# SiC780.net
KiCad netlist of a schematic drawn in Altium Designer
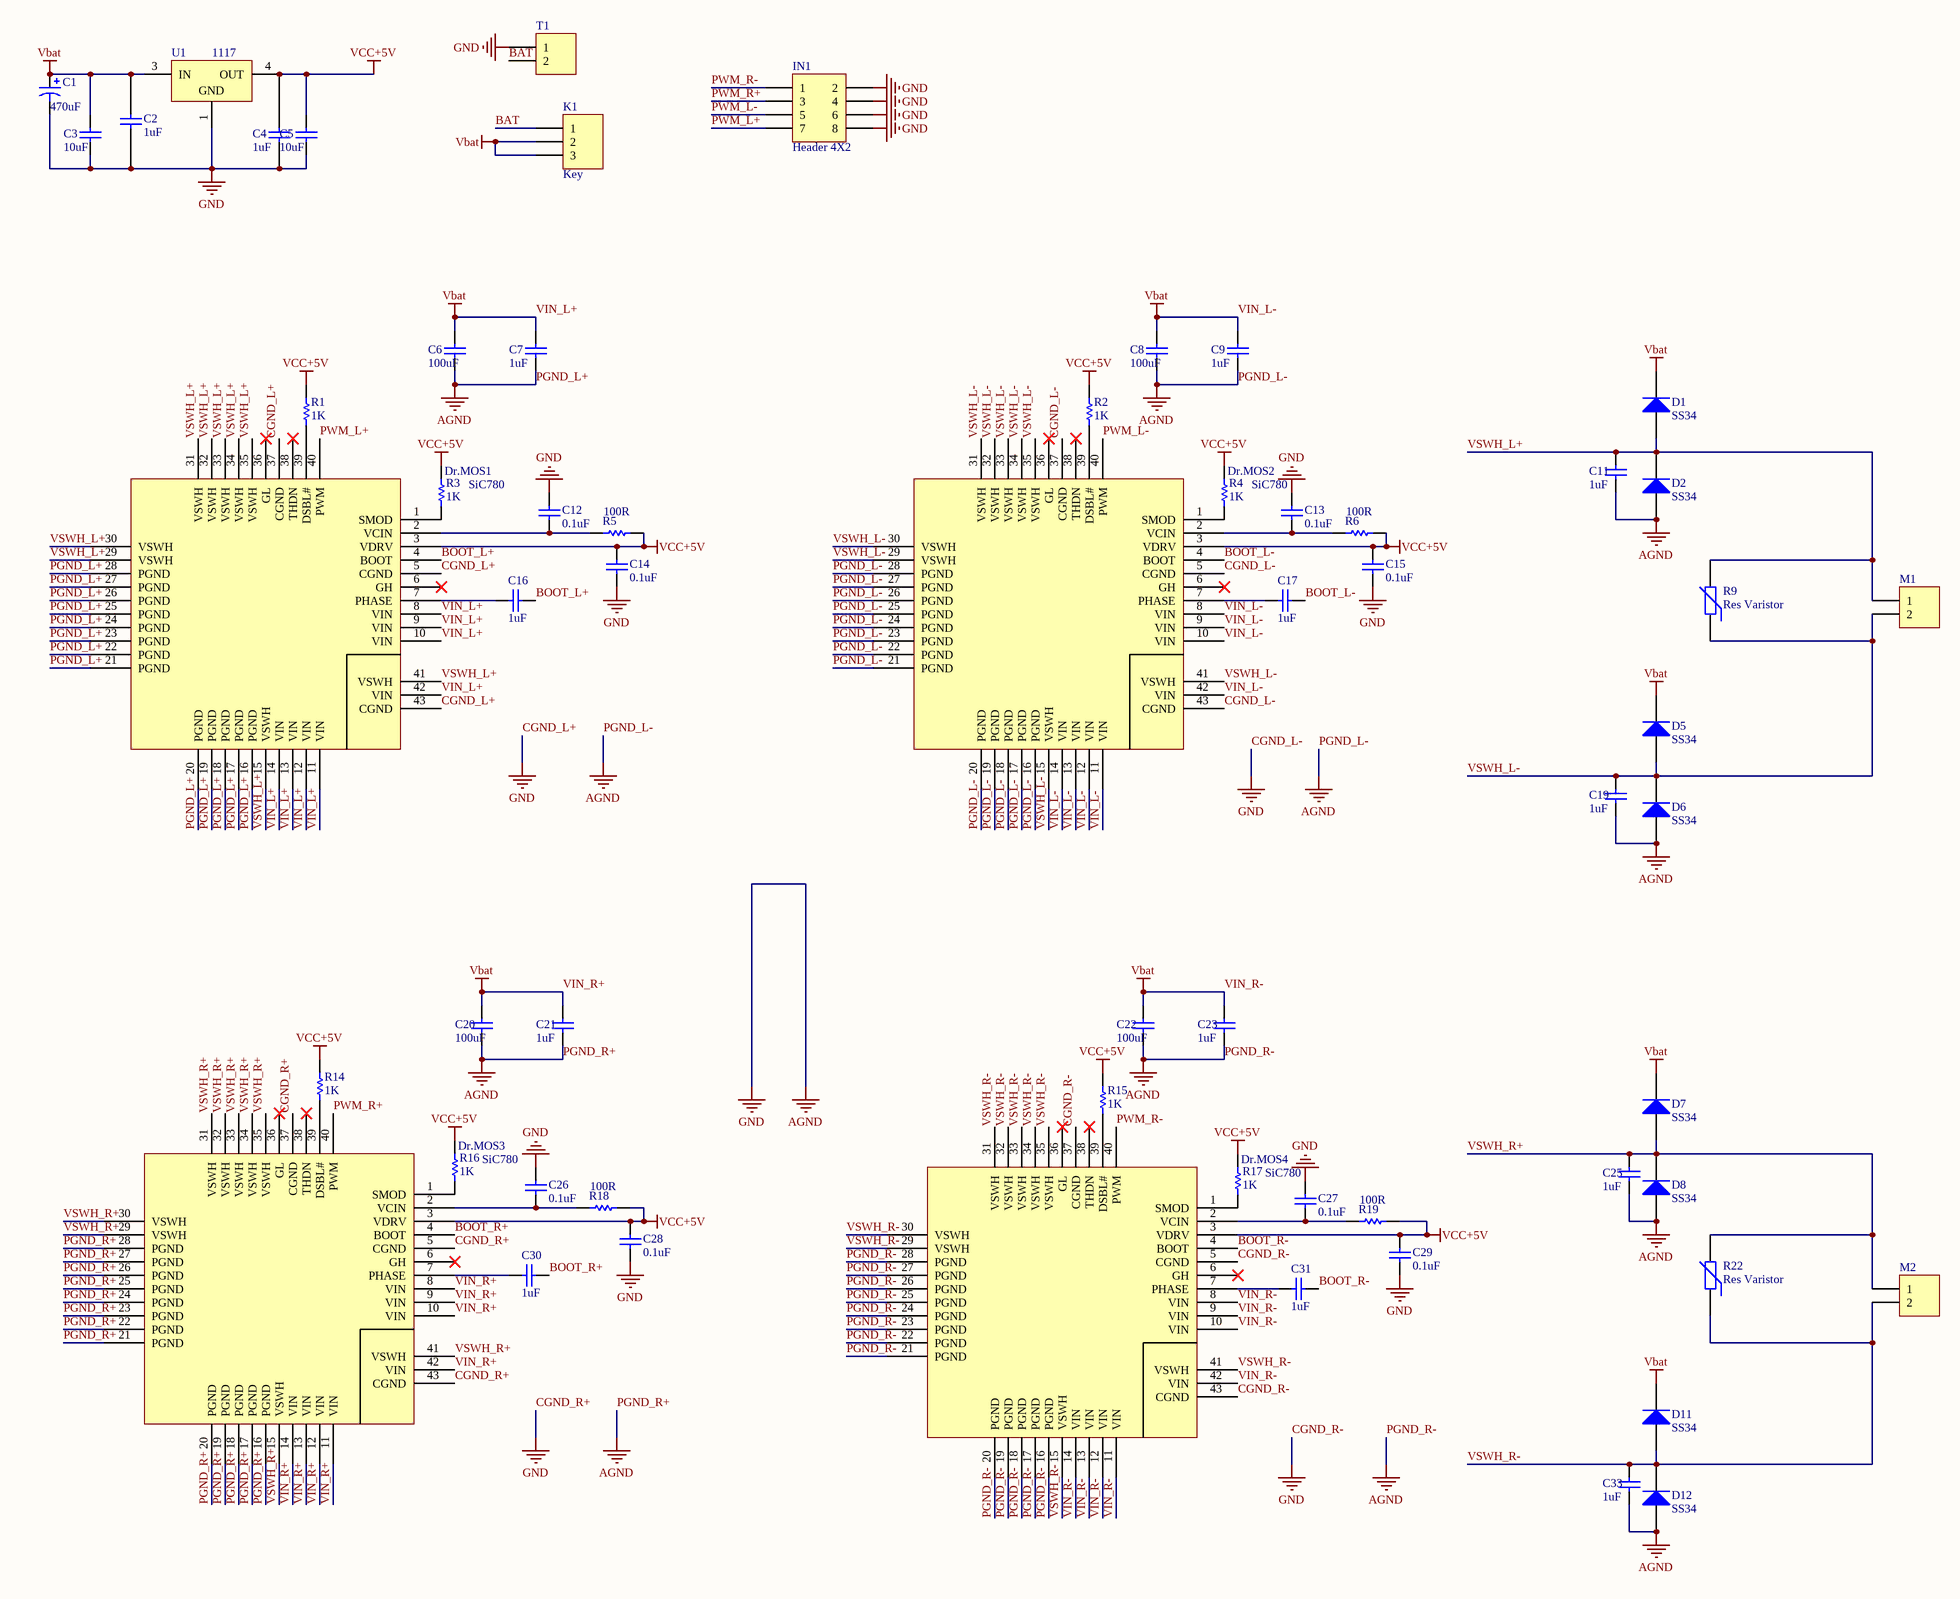
[diagram p0: SiC780驱动.SchDoc]

(export (version "E")
  (design (tool "Eeschema 10.0.6"))
  (components
    (comp (ref "C1")
      (value "470uF")
      (footprint "CAP")
      (description "Polarized Capacitor (Surface Mount)")
      (fields (field (name "Comment") "470uf") (field (name "PUBLISHER") "Altium Limited"))
      (libsource (lib "Miscellaneous Devices") (part "Cap Pol3"))
    )
    (comp (ref "C2")
      (value "1uF")
      (footprint "0603_C")
      (description "Capacitor")
      (fields (field (name "PUBLISHER") "Altium Limited"))
      (libsource (lib "Miscellaneous Devices") (part "Cap"))
    )
    (comp (ref "C3")
      (value "10uF")
      (footprint "1206_C")
      (description "Capacitor")
      (fields (field (name "PUBLISHER") "Altium Limited"))
      (libsource (lib "Miscellaneous Devices") (part "Cap"))
    )
    (comp (ref "C4")
      (value "1uF")
      (footprint "0603_C")
      (description "Capacitor")
      (fields (field (name "PUBLISHER") "Altium Limited"))
      (libsource (lib "Miscellaneous Devices") (part "Cap"))
    )
    (comp (ref "C5")
      (value "10uF")
      (footprint "1206_C")
      (description "Capacitor")
      (fields (field (name "PUBLISHER") "Altium Limited"))
      (libsource (lib "Miscellaneous Devices") (part "Cap"))
    )
    (comp (ref "C6")
      (value "100uF")
      (footprint "1206_C")
      (description "Capacitor")
      (fields (field (name "PUBLISHER") "Altium Limited"))
      (libsource (lib "Miscellaneous Devices") (part "Cap"))
    )
    (comp (ref "C7")
      (value "1uF")
      (footprint "0603_C")
      (description "Capacitor")
      (fields (field (name "PUBLISHER") "Altium Limited"))
      (libsource (lib "Miscellaneous Devices") (part "Cap"))
    )
    (comp (ref "C8")
      (value "100uF")
      (footprint "1206_C")
      (description "Capacitor")
      (fields (field (name "PUBLISHER") "Altium Limited"))
      (libsource (lib "Miscellaneous Devices") (part "Cap"))
    )
    (comp (ref "C9")
      (value "1uF")
      (footprint "0603_C")
      (description "Capacitor")
      (fields (field (name "PUBLISHER") "Altium Limited"))
      (libsource (lib "Miscellaneous Devices") (part "Cap"))
    )
    (comp (ref "C11")
      (value "1uF")
      (footprint "0603_C")
      (description "Capacitor")
      (fields (field (name "PUBLISHER") "Altium Limited"))
      (libsource (lib "Miscellaneous Devices") (part "Cap"))
    )
    (comp (ref "C12")
      (value "0.1uF")
      (footprint "0603_C")
      (description "Capacitor")
      (fields (field (name "PUBLISHER") "Altium Limited"))
      (libsource (lib "Miscellaneous Devices") (part "Cap"))
    )
    (comp (ref "C13")
      (value "0.1uF")
      (footprint "0603_C")
      (description "Capacitor")
      (fields (field (name "PUBLISHER") "Altium Limited"))
      (libsource (lib "Miscellaneous Devices") (part "Cap"))
    )
    (comp (ref "C14")
      (value "0.1uF")
      (footprint "0603_C")
      (description "Capacitor")
      (fields (field (name "PUBLISHER") "Altium Limited"))
      (libsource (lib "Miscellaneous Devices") (part "Cap"))
    )
    (comp (ref "C15")
      (value "0.1uF")
      (footprint "0603_C")
      (description "Capacitor")
      (fields (field (name "PUBLISHER") "Altium Limited"))
      (libsource (lib "Miscellaneous Devices") (part "Cap"))
    )
    (comp (ref "C16")
      (value "1uF")
      (footprint "0603_C")
      (description "Capacitor")
      (fields (field (name "Comment") "0.1uF") (field (name "PUBLISHER") "Altium Limited"))
      (libsource (lib "Miscellaneous Devices") (part "Cap"))
    )
    (comp (ref "C17")
      (value "1uF")
      (footprint "0603_C")
      (description "Capacitor")
      (fields (field (name "Comment") "0.1uF") (field (name "PUBLISHER") "Altium Limited"))
      (libsource (lib "Miscellaneous Devices") (part "Cap"))
    )
    (comp (ref "C19")
      (value "1uF")
      (footprint "0603_C")
      (description "Capacitor")
      (fields (field (name "PUBLISHER") "Altium Limited"))
      (libsource (lib "Miscellaneous Devices") (part "Cap"))
    )
    (comp (ref "C20")
      (value "100uF")
      (footprint "1206_C")
      (description "Capacitor")
      (fields (field (name "PUBLISHER") "Altium Limited"))
      (libsource (lib "Miscellaneous Devices") (part "Cap"))
    )
    (comp (ref "C21")
      (value "1uF")
      (footprint "0603_C")
      (description "Capacitor")
      (fields (field (name "PUBLISHER") "Altium Limited"))
      (libsource (lib "Miscellaneous Devices") (part "Cap"))
    )
    (comp (ref "C22")
      (value "100uF")
      (footprint "1206_C")
      (description "Capacitor")
      (fields (field (name "PUBLISHER") "Altium Limited"))
      (libsource (lib "Miscellaneous Devices") (part "Cap"))
    )
    (comp (ref "C23")
      (value "1uF")
      (footprint "0603_C")
      (description "Capacitor")
      (fields (field (name "PUBLISHER") "Altium Limited"))
      (libsource (lib "Miscellaneous Devices") (part "Cap"))
    )
    (comp (ref "C25")
      (value "1uF")
      (footprint "0603_C")
      (description "Capacitor")
      (fields (field (name "PUBLISHER") "Altium Limited"))
      (libsource (lib "Miscellaneous Devices") (part "Cap"))
    )
    (comp (ref "C26")
      (value "0.1uF")
      (footprint "0603_C")
      (description "Capacitor")
      (fields (field (name "PUBLISHER") "Altium Limited"))
      (libsource (lib "Miscellaneous Devices") (part "Cap"))
    )
    (comp (ref "C27")
      (value "0.1uF")
      (footprint "0603_C")
      (description "Capacitor")
      (fields (field (name "PUBLISHER") "Altium Limited"))
      (libsource (lib "Miscellaneous Devices") (part "Cap"))
    )
    (comp (ref "C28")
      (value "0.1uF")
      (footprint "0603_C")
      (description "Capacitor")
      (fields (field (name "PUBLISHER") "Altium Limited"))
      (libsource (lib "Miscellaneous Devices") (part "Cap"))
    )
    (comp (ref "C29")
      (value "0.1uF")
      (footprint "0603_C")
      (description "Capacitor")
      (fields (field (name "PUBLISHER") "Altium Limited"))
      (libsource (lib "Miscellaneous Devices") (part "Cap"))
    )
    (comp (ref "C30")
      (value "1uF")
      (footprint "0603_C")
      (description "Capacitor")
      (fields (field (name "Comment") "0.1uF") (field (name "PUBLISHER") "Altium Limited"))
      (libsource (lib "Miscellaneous Devices") (part "Cap"))
    )
    (comp (ref "C31")
      (value "1uF")
      (footprint "0603_C")
      (description "Capacitor")
      (fields (field (name "Comment") "0.1uF") (field (name "PUBLISHER") "Altium Limited"))
      (libsource (lib "Miscellaneous Devices") (part "Cap"))
    )
    (comp (ref "C33")
      (value "1uF")
      (footprint "0603_C")
      (description "Capacitor")
      (fields (field (name "PUBLISHER") "Altium Limited"))
      (libsource (lib "Miscellaneous Devices") (part "Cap"))
    )
    (comp (ref "D1")
      (value "SS34")
      (footprint "Diode-1N5189  5*1.5mm")
      (libsource (lib "12届光电双电机MOS驱动") (part "Diode"))
    )
    (comp (ref "D2")
      (value "SS34")
      (footprint "Diode-1N5189  5*1.5mm")
      (libsource (lib "12届光电双电机MOS驱动") (part "Diode"))
    )
    (comp (ref "D5")
      (value "SS34")
      (footprint "Diode-1N5189  5*1.5mm")
      (libsource (lib "12届光电双电机MOS驱动") (part "Diode"))
    )
    (comp (ref "D6")
      (value "SS34")
      (footprint "Diode-1N5189  5*1.5mm")
      (libsource (lib "12届光电双电机MOS驱动") (part "Diode"))
    )
    (comp (ref "D7")
      (value "SS34")
      (footprint "Diode-1N5189  5*1.5mm")
      (libsource (lib "12届光电双电机MOS驱动") (part "Diode"))
    )
    (comp (ref "D8")
      (value "SS34")
      (footprint "Diode-1N5189  5*1.5mm")
      (libsource (lib "12届光电双电机MOS驱动") (part "Diode"))
    )
    (comp (ref "D11")
      (value "SS34")
      (footprint "Diode-1N5189  5*1.5mm")
      (libsource (lib "12届光电双电机MOS驱动") (part "Diode"))
    )
    (comp (ref "D12")
      (value "SS34")
      (footprint "Diode-1N5189  5*1.5mm")
      (libsource (lib "12届光电双电机MOS驱动") (part "Diode"))
    )
    (comp (ref "Dr.MOS1")
      (value "SiC780")
      (footprint "SiC780_new")
      (libsource (lib "SiC780") (part "SiC780"))
    )
    (comp (ref "Dr.MOS2")
      (value "SiC780")
      (footprint "SiC780_new")
      (libsource (lib "SiC780") (part "SiC780"))
    )
    (comp (ref "Dr.MOS3")
      (value "SiC780")
      (footprint "SiC780_new")
      (libsource (lib "SiC780") (part "SiC780"))
    )
    (comp (ref "Dr.MOS4")
      (value "SiC780")
      (footprint "SiC780_new")
      (libsource (lib "SiC780") (part "SiC780"))
    )
    (comp (ref "IN1")
      (value "Header 4X2")
      (footprint "HDR2X4_3D")
      (description "Header, 4-Pin, Dual row")
      (fields (field (name "PUBLISHER") "Altium Limited"))
      (libsource (lib "Miscellaneous Connectors") (part "Header 4X2"))
    )
    (comp (ref "K1")
      (value "Key")
      (footprint "SW-M")
      (description "Header, 3-Pin")
      (fields (field (name "PUBLISHER") "Altium Limited"))
      (libsource (lib "Miscellaneous Connectors") (part "Header 3"))
    )
    (comp (ref "M1")
      (value "~")
      (footprint "KF301-2P")
      (description "Header, 2-Pin")
      (fields (field (name "PUBLISHER") "Altium Limited"))
      (libsource (lib "Miscellaneous Connectors") (part "Header 2"))
    )
    (comp (ref "M2")
      (value "~")
      (footprint "KF301-2P")
      (description "Header, 2-Pin")
      (fields (field (name "PUBLISHER") "Altium Limited"))
      (libsource (lib "Miscellaneous Connectors") (part "Header 2"))
    )
    (comp (ref "R1")
      (value "1K")
      (footprint "R0603")
      (description "Resistor")
      (fields (field (name "PUBLISHER") "Altium Limited"))
      (libsource (lib "Miscellaneous Devices") (part "Res1"))
    )
    (comp (ref "R2")
      (value "1K")
      (footprint "R0603")
      (description "Resistor")
      (fields (field (name "PUBLISHER") "Altium Limited"))
      (libsource (lib "Miscellaneous Devices") (part "Res1"))
    )
    (comp (ref "R3")
      (value "1K")
      (footprint "R0603")
      (description "Resistor")
      (fields (field (name "PUBLISHER") "Altium Limited"))
      (libsource (lib "Miscellaneous Devices") (part "Res1"))
    )
    (comp (ref "R4")
      (value "1K")
      (footprint "R0603")
      (description "Resistor")
      (fields (field (name "PUBLISHER") "Altium Limited"))
      (libsource (lib "Miscellaneous Devices") (part "Res1"))
    )
    (comp (ref "R5")
      (value "100R")
      (footprint "R0603")
      (description "Resistor")
      (fields (field (name "PUBLISHER") "Altium Limited"))
      (libsource (lib "Miscellaneous Devices") (part "Res1"))
    )
    (comp (ref "R6")
      (value "100R")
      (footprint "R0603")
      (description "Resistor")
      (fields (field (name "PUBLISHER") "Altium Limited"))
      (libsource (lib "Miscellaneous Devices") (part "Res1"))
    )
    (comp (ref "R9")
      (value "Res Varistor")
      (footprint "6-0805_N")
      (description "Varistor (Voltage-Sensitive Resistor)")
      (fields (field (name "PUBLISHER") "Altium Limited"))
      (libsource (lib "Miscellaneous Devices") (part "Res Varistor"))
    )
    (comp (ref "R14")
      (value "1K")
      (footprint "R0603")
      (description "Resistor")
      (fields (field (name "PUBLISHER") "Altium Limited"))
      (libsource (lib "Miscellaneous Devices") (part "Res1"))
    )
    (comp (ref "R15")
      (value "1K")
      (footprint "R0603")
      (description "Resistor")
      (fields (field (name "PUBLISHER") "Altium Limited"))
      (libsource (lib "Miscellaneous Devices") (part "Res1"))
    )
    (comp (ref "R16")
      (value "1K")
      (footprint "R0603")
      (description "Resistor")
      (fields (field (name "PUBLISHER") "Altium Limited"))
      (libsource (lib "Miscellaneous Devices") (part "Res1"))
    )
    (comp (ref "R17")
      (value "1K")
      (footprint "R0603")
      (description "Resistor")
      (fields (field (name "PUBLISHER") "Altium Limited"))
      (libsource (lib "Miscellaneous Devices") (part "Res1"))
    )
    (comp (ref "R18")
      (value "100R")
      (footprint "R0603")
      (description "Resistor")
      (fields (field (name "PUBLISHER") "Altium Limited"))
      (libsource (lib "Miscellaneous Devices") (part "Res1"))
    )
    (comp (ref "R19")
      (value "100R")
      (footprint "R0603")
      (description "Resistor")
      (fields (field (name "PUBLISHER") "Altium Limited"))
      (libsource (lib "Miscellaneous Devices") (part "Res1"))
    )
    (comp (ref "R22")
      (value "Res Varistor")
      (footprint "6-0805_N")
      (description "Varistor (Voltage-Sensitive Resistor)")
      (fields (field (name "PUBLISHER") "Altium Limited"))
      (libsource (lib "Miscellaneous Devices") (part "Res Varistor"))
    )
    (comp (ref "T1")
      (value "~")
      (footprint "KF301-2P")
      (description "Header, 2-Pin")
      (fields (field (name "PUBLISHER") "Altium Limited"))
      (libsource (lib "Miscellaneous Connectors") (part "Header 2"))
    )
    (comp (ref "U1")
      (value "1117")
      (footprint "SOT223_N")
      (description "800mA Low-Dropout Linear Regulator")
      (fields
        (field (name "PARTNUMBER") "LM1117DT-3.3")
        (field (name "MANUFACTURER") "National Semiconductor")
        (field (name "PUBLISHER") "Altium Limited")
      )
      (libsource (lib "NSC LDO") (part "LM1117DT-3.3"))
    )
  )
  (nets
    (net (code "1") (name "/BAT") (class "Default")
      (node (ref "K1") (pin "1") (pinfunction "1_1") (pintype "passive"))
      (node (ref "T1") (pin "2") (pinfunction "2_2") (pintype "passive"))
    )
    (net (code "2") (name "/BOOT_L+") (class "Default")
      (node (ref "C16") (pin "2") (pinfunction "2_2") (pintype "passive"))
      (node (ref "Dr.MOS1") (pin "4") (pinfunction "BOOT_4") (pintype "passive"))
    )
    (net (code "3") (name "/BOOT_L-") (class "Default")
      (node (ref "C17") (pin "2") (pinfunction "2_2") (pintype "passive"))
      (node (ref "Dr.MOS2") (pin "4") (pinfunction "BOOT_4") (pintype "passive"))
    )
    (net (code "4") (name "/BOOT_R+") (class "Default")
      (node (ref "C30") (pin "2") (pinfunction "2_2") (pintype "passive"))
      (node (ref "Dr.MOS3") (pin "4") (pinfunction "BOOT_4") (pintype "passive"))
    )
    (net (code "5") (name "/BOOT_R-") (class "Default")
      (node (ref "C31") (pin "2") (pinfunction "2_2") (pintype "passive"))
      (node (ref "Dr.MOS4") (pin "4") (pinfunction "BOOT_4") (pintype "passive"))
    )
    (net (code "6") (name "/PWM_L+") (class "Default")
      (node (ref "Dr.MOS1") (pin "40") (pinfunction "PWM_40") (pintype "passive"))
      (node (ref "IN1") (pin "7") (pinfunction "7_7") (pintype "passive"))
    )
    (net (code "7") (name "/PWM_L-") (class "Default")
      (node (ref "Dr.MOS2") (pin "40") (pinfunction "PWM_40") (pintype "passive"))
      (node (ref "IN1") (pin "5") (pinfunction "5_5") (pintype "passive"))
    )
    (net (code "8") (name "/PWM_R+") (class "Default")
      (node (ref "Dr.MOS3") (pin "40") (pinfunction "PWM_40") (pintype "passive"))
      (node (ref "IN1") (pin "3") (pinfunction "3_3") (pintype "passive"))
    )
    (net (code "9") (name "/PWM_R-") (class "Default")
      (node (ref "Dr.MOS4") (pin "40") (pinfunction "PWM_40") (pintype "passive"))
      (node (ref "IN1") (pin "1") (pinfunction "1_1") (pintype "passive"))
    )
    (net (code "10") (name "/VSWH_L+") (class "Default")
      (node (ref "C11") (pin "1") (pinfunction "1_1") (pintype "passive"))
      (node (ref "D1") (pin "1") (pinfunction "A_1") (pintype "passive"))
      (node (ref "D2") (pin "2") (pinfunction "K_2") (pintype "passive"))
      (node (ref "Dr.MOS1") (pin "15") (pinfunction "VSWH_15") (pintype "passive"))
      (node (ref "Dr.MOS1") (pin "29") (pinfunction "VSWH_29") (pintype "passive"))
      (node (ref "Dr.MOS1") (pin "30") (pinfunction "VSWH_30") (pintype "passive"))
      (node (ref "Dr.MOS1") (pin "31") (pinfunction "VSWH_31") (pintype "passive"))
      (node (ref "Dr.MOS1") (pin "32") (pinfunction "VSWH_32") (pintype "passive"))
      (node (ref "Dr.MOS1") (pin "33") (pinfunction "VSWH_33") (pintype "passive"))
      (node (ref "Dr.MOS1") (pin "34") (pinfunction "VSWH_34") (pintype "passive"))
      (node (ref "Dr.MOS1") (pin "35") (pinfunction "VSWH_35") (pintype "passive"))
      (node (ref "Dr.MOS1") (pin "41") (pinfunction "VSWH_41") (pintype "passive"))
      (node (ref "M1") (pin "1") (pinfunction "1_1") (pintype "passive"))
      (node (ref "R9") (pin "2") (pinfunction "2_2") (pintype "passive"))
    )
    (net (code "11") (name "/VSWH_L-") (class "Default")
      (node (ref "C19") (pin "1") (pinfunction "1_1") (pintype "passive"))
      (node (ref "D5") (pin "1") (pinfunction "A_1") (pintype "passive"))
      (node (ref "D6") (pin "2") (pinfunction "K_2") (pintype "passive"))
      (node (ref "Dr.MOS2") (pin "15") (pinfunction "VSWH_15") (pintype "passive"))
      (node (ref "Dr.MOS2") (pin "29") (pinfunction "VSWH_29") (pintype "passive"))
      (node (ref "Dr.MOS2") (pin "30") (pinfunction "VSWH_30") (pintype "passive"))
      (node (ref "Dr.MOS2") (pin "31") (pinfunction "VSWH_31") (pintype "passive"))
      (node (ref "Dr.MOS2") (pin "32") (pinfunction "VSWH_32") (pintype "passive"))
      (node (ref "Dr.MOS2") (pin "33") (pinfunction "VSWH_33") (pintype "passive"))
      (node (ref "Dr.MOS2") (pin "34") (pinfunction "VSWH_34") (pintype "passive"))
      (node (ref "Dr.MOS2") (pin "35") (pinfunction "VSWH_35") (pintype "passive"))
      (node (ref "Dr.MOS2") (pin "41") (pinfunction "VSWH_41") (pintype "passive"))
      (node (ref "M1") (pin "2") (pinfunction "2_2") (pintype "passive"))
      (node (ref "R9") (pin "1") (pinfunction "1_1") (pintype "passive"))
    )
    (net (code "12") (name "/VSWH_R+") (class "Default")
      (node (ref "C25") (pin "1") (pinfunction "1_1") (pintype "passive"))
      (node (ref "D7") (pin "1") (pinfunction "A_1") (pintype "passive"))
      (node (ref "D8") (pin "2") (pinfunction "K_2") (pintype "passive"))
      (node (ref "Dr.MOS3") (pin "15") (pinfunction "VSWH_15") (pintype "passive"))
      (node (ref "Dr.MOS3") (pin "29") (pinfunction "VSWH_29") (pintype "passive"))
      (node (ref "Dr.MOS3") (pin "30") (pinfunction "VSWH_30") (pintype "passive"))
      (node (ref "Dr.MOS3") (pin "31") (pinfunction "VSWH_31") (pintype "passive"))
      (node (ref "Dr.MOS3") (pin "32") (pinfunction "VSWH_32") (pintype "passive"))
      (node (ref "Dr.MOS3") (pin "33") (pinfunction "VSWH_33") (pintype "passive"))
      (node (ref "Dr.MOS3") (pin "34") (pinfunction "VSWH_34") (pintype "passive"))
      (node (ref "Dr.MOS3") (pin "35") (pinfunction "VSWH_35") (pintype "passive"))
      (node (ref "Dr.MOS3") (pin "41") (pinfunction "VSWH_41") (pintype "passive"))
      (node (ref "M2") (pin "1") (pinfunction "1_1") (pintype "passive"))
      (node (ref "R22") (pin "2") (pinfunction "2_2") (pintype "passive"))
    )
    (net (code "13") (name "/VSWH_R-") (class "Default")
      (node (ref "C33") (pin "1") (pinfunction "1_1") (pintype "passive"))
      (node (ref "D11") (pin "1") (pinfunction "A_1") (pintype "passive"))
      (node (ref "D12") (pin "2") (pinfunction "K_2") (pintype "passive"))
      (node (ref "Dr.MOS4") (pin "15") (pinfunction "VSWH_15") (pintype "passive"))
      (node (ref "Dr.MOS4") (pin "29") (pinfunction "VSWH_29") (pintype "passive"))
      (node (ref "Dr.MOS4") (pin "30") (pinfunction "VSWH_30") (pintype "passive"))
      (node (ref "Dr.MOS4") (pin "31") (pinfunction "VSWH_31") (pintype "passive"))
      (node (ref "Dr.MOS4") (pin "32") (pinfunction "VSWH_32") (pintype "passive"))
      (node (ref "Dr.MOS4") (pin "33") (pinfunction "VSWH_33") (pintype "passive"))
      (node (ref "Dr.MOS4") (pin "34") (pinfunction "VSWH_34") (pintype "passive"))
      (node (ref "Dr.MOS4") (pin "35") (pinfunction "VSWH_35") (pintype "passive"))
      (node (ref "Dr.MOS4") (pin "41") (pinfunction "VSWH_41") (pintype "passive"))
      (node (ref "M2") (pin "2") (pinfunction "2_2") (pintype "passive"))
      (node (ref "R22") (pin "1") (pinfunction "1_1") (pintype "passive"))
    )
    (net (code "14") (name "AGND") (class "Default")
      (node (ref "C1") (pin "2") (pinfunction "2_2") (pintype "passive"))
      (node (ref "C11") (pin "2") (pinfunction "2_2") (pintype "passive"))
      (node (ref "C12") (pin "1") (pinfunction "1_1") (pintype "passive"))
      (node (ref "C13") (pin "1") (pinfunction "1_1") (pintype "passive"))
      (node (ref "C14") (pin "1") (pinfunction "1_1") (pintype "passive"))
      (node (ref "C15") (pin "1") (pinfunction "1_1") (pintype "passive"))
      (node (ref "C19") (pin "2") (pinfunction "2_2") (pintype "passive"))
      (node (ref "C2") (pin "1") (pinfunction "1_1") (pintype "passive"))
      (node (ref "C20") (pin "2") (pinfunction "2_2") (pintype "passive"))
      (node (ref "C21") (pin "2") (pinfunction "2_2") (pintype "passive"))
      (node (ref "C22") (pin "2") (pinfunction "2_2") (pintype "passive"))
      (node (ref "C23") (pin "2") (pinfunction "2_2") (pintype "passive"))
      (node (ref "C25") (pin "2") (pinfunction "2_2") (pintype "passive"))
      (node (ref "C26") (pin "1") (pinfunction "1_1") (pintype "passive"))
      (node (ref "C27") (pin "1") (pinfunction "1_1") (pintype "passive"))
      (node (ref "C28") (pin "1") (pinfunction "1_1") (pintype "passive"))
      (node (ref "C29") (pin "1") (pinfunction "1_1") (pintype "passive"))
      (node (ref "C3") (pin "2") (pinfunction "2_2") (pintype "passive"))
      (node (ref "C33") (pin "2") (pinfunction "2_2") (pintype "passive"))
      (node (ref "C4") (pin "2") (pinfunction "2_2") (pintype "passive"))
      (node (ref "C5") (pin "2") (pinfunction "2_2") (pintype "passive"))
      (node (ref "C6") (pin "2") (pinfunction "2_2") (pintype "passive"))
      (node (ref "C7") (pin "2") (pinfunction "2_2") (pintype "passive"))
      (node (ref "C8") (pin "2") (pinfunction "2_2") (pintype "passive"))
      (node (ref "C9") (pin "2") (pinfunction "2_2") (pintype "passive"))
      (node (ref "D12") (pin "1") (pinfunction "A_1") (pintype "passive"))
      (node (ref "D2") (pin "1") (pinfunction "A_1") (pintype "passive"))
      (node (ref "D6") (pin "1") (pinfunction "A_1") (pintype "passive"))
      (node (ref "D8") (pin "1") (pinfunction "A_1") (pintype "passive"))
      (node (ref "Dr.MOS1") (pin "16") (pinfunction "PGND_16") (pintype "passive"))
      (node (ref "Dr.MOS1") (pin "17") (pinfunction "PGND_17") (pintype "passive"))
      (node (ref "Dr.MOS1") (pin "18") (pinfunction "PGND_18") (pintype "passive"))
      (node (ref "Dr.MOS1") (pin "19") (pinfunction "PGND_19") (pintype "passive"))
      (node (ref "Dr.MOS1") (pin "20") (pinfunction "PGND_20") (pintype "passive"))
      (node (ref "Dr.MOS1") (pin "21") (pinfunction "PGND_21") (pintype "passive"))
      (node (ref "Dr.MOS1") (pin "22") (pinfunction "PGND_22") (pintype "passive"))
      (node (ref "Dr.MOS1") (pin "23") (pinfunction "PGND_23") (pintype "passive"))
      (node (ref "Dr.MOS1") (pin "24") (pinfunction "PGND_24") (pintype "passive"))
      (node (ref "Dr.MOS1") (pin "25") (pinfunction "PGND_25") (pintype "passive"))
      (node (ref "Dr.MOS1") (pin "26") (pinfunction "PGND_26") (pintype "passive"))
      (node (ref "Dr.MOS1") (pin "27") (pinfunction "PGND_27") (pintype "passive"))
      (node (ref "Dr.MOS1") (pin "28") (pinfunction "PGND_28") (pintype "passive"))
      (node (ref "Dr.MOS1") (pin "37") (pinfunction "CGND_37") (pintype "passive"))
      (node (ref "Dr.MOS1") (pin "43") (pinfunction "CGND_43") (pintype "passive"))
      (node (ref "Dr.MOS1") (pin "5") (pinfunction "CGND_5") (pintype "passive"))
      (node (ref "Dr.MOS2") (pin "16") (pinfunction "PGND_16") (pintype "passive"))
      (node (ref "Dr.MOS2") (pin "17") (pinfunction "PGND_17") (pintype "passive"))
      (node (ref "Dr.MOS2") (pin "18") (pinfunction "PGND_18") (pintype "passive"))
      (node (ref "Dr.MOS2") (pin "19") (pinfunction "PGND_19") (pintype "passive"))
      (node (ref "Dr.MOS2") (pin "20") (pinfunction "PGND_20") (pintype "passive"))
      (node (ref "Dr.MOS2") (pin "21") (pinfunction "PGND_21") (pintype "passive"))
      (node (ref "Dr.MOS2") (pin "22") (pinfunction "PGND_22") (pintype "passive"))
      (node (ref "Dr.MOS2") (pin "23") (pinfunction "PGND_23") (pintype "passive"))
      (node (ref "Dr.MOS2") (pin "24") (pinfunction "PGND_24") (pintype "passive"))
      (node (ref "Dr.MOS2") (pin "25") (pinfunction "PGND_25") (pintype "passive"))
      (node (ref "Dr.MOS2") (pin "26") (pinfunction "PGND_26") (pintype "passive"))
      (node (ref "Dr.MOS2") (pin "27") (pinfunction "PGND_27") (pintype "passive"))
      (node (ref "Dr.MOS2") (pin "28") (pinfunction "PGND_28") (pintype "passive"))
      (node (ref "Dr.MOS2") (pin "37") (pinfunction "CGND_37") (pintype "passive"))
      (node (ref "Dr.MOS2") (pin "43") (pinfunction "CGND_43") (pintype "passive"))
      (node (ref "Dr.MOS2") (pin "5") (pinfunction "CGND_5") (pintype "passive"))
      (node (ref "Dr.MOS3") (pin "16") (pinfunction "PGND_16") (pintype "passive"))
      (node (ref "Dr.MOS3") (pin "17") (pinfunction "PGND_17") (pintype "passive"))
      (node (ref "Dr.MOS3") (pin "18") (pinfunction "PGND_18") (pintype "passive"))
      (node (ref "Dr.MOS3") (pin "19") (pinfunction "PGND_19") (pintype "passive"))
      (node (ref "Dr.MOS3") (pin "20") (pinfunction "PGND_20") (pintype "passive"))
      (node (ref "Dr.MOS3") (pin "21") (pinfunction "PGND_21") (pintype "passive"))
      (node (ref "Dr.MOS3") (pin "22") (pinfunction "PGND_22") (pintype "passive"))
      (node (ref "Dr.MOS3") (pin "23") (pinfunction "PGND_23") (pintype "passive"))
      (node (ref "Dr.MOS3") (pin "24") (pinfunction "PGND_24") (pintype "passive"))
      (node (ref "Dr.MOS3") (pin "25") (pinfunction "PGND_25") (pintype "passive"))
      (node (ref "Dr.MOS3") (pin "26") (pinfunction "PGND_26") (pintype "passive"))
      (node (ref "Dr.MOS3") (pin "27") (pinfunction "PGND_27") (pintype "passive"))
      (node (ref "Dr.MOS3") (pin "28") (pinfunction "PGND_28") (pintype "passive"))
      (node (ref "Dr.MOS3") (pin "37") (pinfunction "CGND_37") (pintype "passive"))
      (node (ref "Dr.MOS3") (pin "43") (pinfunction "CGND_43") (pintype "passive"))
      (node (ref "Dr.MOS3") (pin "5") (pinfunction "CGND_5") (pintype "passive"))
      (node (ref "Dr.MOS4") (pin "16") (pinfunction "PGND_16") (pintype "passive"))
      (node (ref "Dr.MOS4") (pin "17") (pinfunction "PGND_17") (pintype "passive"))
      (node (ref "Dr.MOS4") (pin "18") (pinfunction "PGND_18") (pintype "passive"))
      (node (ref "Dr.MOS4") (pin "19") (pinfunction "PGND_19") (pintype "passive"))
      (node (ref "Dr.MOS4") (pin "20") (pinfunction "PGND_20") (pintype "passive"))
      (node (ref "Dr.MOS4") (pin "21") (pinfunction "PGND_21") (pintype "passive"))
      (node (ref "Dr.MOS4") (pin "22") (pinfunction "PGND_22") (pintype "passive"))
      (node (ref "Dr.MOS4") (pin "23") (pinfunction "PGND_23") (pintype "passive"))
      (node (ref "Dr.MOS4") (pin "24") (pinfunction "PGND_24") (pintype "passive"))
      (node (ref "Dr.MOS4") (pin "25") (pinfunction "PGND_25") (pintype "passive"))
      (node (ref "Dr.MOS4") (pin "26") (pinfunction "PGND_26") (pintype "passive"))
      (node (ref "Dr.MOS4") (pin "27") (pinfunction "PGND_27") (pintype "passive"))
      (node (ref "Dr.MOS4") (pin "28") (pinfunction "PGND_28") (pintype "passive"))
      (node (ref "Dr.MOS4") (pin "37") (pinfunction "CGND_37") (pintype "passive"))
      (node (ref "Dr.MOS4") (pin "43") (pinfunction "CGND_43") (pintype "passive"))
      (node (ref "Dr.MOS4") (pin "5") (pinfunction "CGND_5") (pintype "passive"))
      (node (ref "IN1") (pin "2") (pinfunction "2_2") (pintype "passive"))
      (node (ref "IN1") (pin "4") (pinfunction "4_4") (pintype "passive"))
      (node (ref "IN1") (pin "6") (pinfunction "6_6") (pintype "passive"))
      (node (ref "IN1") (pin "8") (pinfunction "8_8") (pintype "passive"))
      (node (ref "T1") (pin "1") (pinfunction "1_1") (pintype "passive"))
      (node (ref "U1") (pin "1") (pinfunction "GND_1") (pintype "power_in"))
    )
    (net (code "15") (name "Net-(Dr.MOS1-DSBL#)") (class "Default")
      (node (ref "Dr.MOS1") (pin "39") (pinfunction "DSBL#_39") (pintype "passive"))
      (node (ref "R1") (pin "2") (pinfunction "2_2") (pintype "passive"))
    )
    (net (code "16") (name "Net-(Dr.MOS1-PHASE)") (class "Default")
      (node (ref "C16") (pin "1") (pinfunction "1_1") (pintype "passive"))
      (node (ref "Dr.MOS1") (pin "7") (pinfunction "PHASE_7") (pintype "passive"))
    )
    (net (code "17") (name "Net-(Dr.MOS1-SMOD)") (class "Default")
      (node (ref "Dr.MOS1") (pin "1") (pinfunction "SMOD_1") (pintype "passive"))
      (node (ref "R3") (pin "2") (pinfunction "2_2") (pintype "passive"))
    )
    (net (code "18") (name "Net-(Dr.MOS1-VCIN)") (class "Default")
      (node (ref "C12") (pin "2") (pinfunction "2_2") (pintype "passive"))
      (node (ref "Dr.MOS1") (pin "2") (pinfunction "VCIN_2") (pintype "passive"))
      (node (ref "R5") (pin "2") (pinfunction "2_2") (pintype "passive"))
    )
    (net (code "19") (name "Net-(Dr.MOS2-DSBL#)") (class "Default")
      (node (ref "Dr.MOS2") (pin "39") (pinfunction "DSBL#_39") (pintype "passive"))
      (node (ref "R2") (pin "2") (pinfunction "2_2") (pintype "passive"))
    )
    (net (code "20") (name "Net-(Dr.MOS2-PHASE)") (class "Default")
      (node (ref "C17") (pin "1") (pinfunction "1_1") (pintype "passive"))
      (node (ref "Dr.MOS2") (pin "7") (pinfunction "PHASE_7") (pintype "passive"))
    )
    (net (code "21") (name "Net-(Dr.MOS2-SMOD)") (class "Default")
      (node (ref "Dr.MOS2") (pin "1") (pinfunction "SMOD_1") (pintype "passive"))
      (node (ref "R4") (pin "2") (pinfunction "2_2") (pintype "passive"))
    )
    (net (code "22") (name "Net-(Dr.MOS2-VCIN)") (class "Default")
      (node (ref "C13") (pin "2") (pinfunction "2_2") (pintype "passive"))
      (node (ref "Dr.MOS2") (pin "2") (pinfunction "VCIN_2") (pintype "passive"))
      (node (ref "R6") (pin "2") (pinfunction "2_2") (pintype "passive"))
    )
    (net (code "23") (name "Net-(Dr.MOS3-DSBL#)") (class "Default")
      (node (ref "Dr.MOS3") (pin "39") (pinfunction "DSBL#_39") (pintype "passive"))
      (node (ref "R14") (pin "2") (pinfunction "2_2") (pintype "passive"))
    )
    (net (code "24") (name "Net-(Dr.MOS3-PHASE)") (class "Default")
      (node (ref "C30") (pin "1") (pinfunction "1_1") (pintype "passive"))
      (node (ref "Dr.MOS3") (pin "7") (pinfunction "PHASE_7") (pintype "passive"))
    )
    (net (code "25") (name "Net-(Dr.MOS3-SMOD)") (class "Default")
      (node (ref "Dr.MOS3") (pin "1") (pinfunction "SMOD_1") (pintype "passive"))
      (node (ref "R16") (pin "2") (pinfunction "2_2") (pintype "passive"))
    )
    (net (code "26") (name "Net-(Dr.MOS3-VCIN)") (class "Default")
      (node (ref "C26") (pin "2") (pinfunction "2_2") (pintype "passive"))
      (node (ref "Dr.MOS3") (pin "2") (pinfunction "VCIN_2") (pintype "passive"))
      (node (ref "R18") (pin "2") (pinfunction "2_2") (pintype "passive"))
    )
    (net (code "27") (name "Net-(Dr.MOS4-DSBL#)") (class "Default")
      (node (ref "Dr.MOS4") (pin "39") (pinfunction "DSBL#_39") (pintype "passive"))
      (node (ref "R15") (pin "2") (pinfunction "2_2") (pintype "passive"))
    )
    (net (code "28") (name "Net-(Dr.MOS4-PHASE)") (class "Default")
      (node (ref "C31") (pin "1") (pinfunction "1_1") (pintype "passive"))
      (node (ref "Dr.MOS4") (pin "7") (pinfunction "PHASE_7") (pintype "passive"))
    )
    (net (code "29") (name "Net-(Dr.MOS4-SMOD)") (class "Default")
      (node (ref "Dr.MOS4") (pin "1") (pinfunction "SMOD_1") (pintype "passive"))
      (node (ref "R17") (pin "2") (pinfunction "2_2") (pintype "passive"))
    )
    (net (code "30") (name "Net-(Dr.MOS4-VCIN)") (class "Default")
      (node (ref "C27") (pin "2") (pinfunction "2_2") (pintype "passive"))
      (node (ref "Dr.MOS4") (pin "2") (pinfunction "VCIN_2") (pintype "passive"))
      (node (ref "R19") (pin "2") (pinfunction "2_2") (pintype "passive"))
    )
    (net (code "31") (name "VCC+5V") (class "Default")
      (node (ref "C14") (pin "2") (pinfunction "2_2") (pintype "passive"))
      (node (ref "C15") (pin "2") (pinfunction "2_2") (pintype "passive"))
      (node (ref "C28") (pin "2") (pinfunction "2_2") (pintype "passive"))
      (node (ref "C29") (pin "2") (pinfunction "2_2") (pintype "passive"))
      (node (ref "C4") (pin "1") (pinfunction "1_1") (pintype "passive"))
      (node (ref "C5") (pin "1") (pinfunction "1_1") (pintype "passive"))
      (node (ref "Dr.MOS1") (pin "3") (pinfunction "VDRV_3") (pintype "passive"))
      (node (ref "Dr.MOS2") (pin "3") (pinfunction "VDRV_3") (pintype "passive"))
      (node (ref "Dr.MOS3") (pin "3") (pinfunction "VDRV_3") (pintype "passive"))
      (node (ref "Dr.MOS4") (pin "3") (pinfunction "VDRV_3") (pintype "passive"))
      (node (ref "R1") (pin "1") (pinfunction "1_1") (pintype "passive"))
      (node (ref "R14") (pin "1") (pinfunction "1_1") (pintype "passive"))
      (node (ref "R15") (pin "1") (pinfunction "1_1") (pintype "passive"))
      (node (ref "R16") (pin "1") (pinfunction "1_1") (pintype "passive"))
      (node (ref "R17") (pin "1") (pinfunction "1_1") (pintype "passive"))
      (node (ref "R18") (pin "1") (pinfunction "1_1") (pintype "passive"))
      (node (ref "R19") (pin "1") (pinfunction "1_1") (pintype "passive"))
      (node (ref "R2") (pin "1") (pinfunction "1_1") (pintype "passive"))
      (node (ref "R3") (pin "1") (pinfunction "1_1") (pintype "passive"))
      (node (ref "R4") (pin "1") (pinfunction "1_1") (pintype "passive"))
      (node (ref "R5") (pin "1") (pinfunction "1_1") (pintype "passive"))
      (node (ref "R6") (pin "1") (pinfunction "1_1") (pintype "passive"))
      (node (ref "U1") (pin "4") (pinfunction "OUT_4") (pintype "power_in"))
    )
    (net (code "32") (name "Vbat") (class "Default")
      (node (ref "C1") (pin "1") (pinfunction "1_1") (pintype "passive"))
      (node (ref "C2") (pin "2") (pinfunction "2_2") (pintype "passive"))
      (node (ref "C20") (pin "1") (pinfunction "1_1") (pintype "passive"))
      (node (ref "C21") (pin "1") (pinfunction "1_1") (pintype "passive"))
      (node (ref "C22") (pin "1") (pinfunction "1_1") (pintype "passive"))
      (node (ref "C23") (pin "1") (pinfunction "1_1") (pintype "passive"))
      (node (ref "C3") (pin "1") (pinfunction "1_1") (pintype "passive"))
      (node (ref "C6") (pin "1") (pinfunction "1_1") (pintype "passive"))
      (node (ref "C7") (pin "1") (pinfunction "1_1") (pintype "passive"))
      (node (ref "C8") (pin "1") (pinfunction "1_1") (pintype "passive"))
      (node (ref "C9") (pin "1") (pinfunction "1_1") (pintype "passive"))
      (node (ref "D1") (pin "2") (pinfunction "K_2") (pintype "passive"))
      (node (ref "D11") (pin "2") (pinfunction "K_2") (pintype "passive"))
      (node (ref "D5") (pin "2") (pinfunction "K_2") (pintype "passive"))
      (node (ref "D7") (pin "2") (pinfunction "K_2") (pintype "passive"))
      (node (ref "Dr.MOS1") (pin "10") (pinfunction "VIN_10") (pintype "passive"))
      (node (ref "Dr.MOS1") (pin "11") (pinfunction "VIN_11") (pintype "passive"))
      (node (ref "Dr.MOS1") (pin "12") (pinfunction "VIN_12") (pintype "passive"))
      (node (ref "Dr.MOS1") (pin "13") (pinfunction "VIN_13") (pintype "passive"))
      (node (ref "Dr.MOS1") (pin "14") (pinfunction "VIN_14") (pintype "passive"))
      (node (ref "Dr.MOS1") (pin "42") (pinfunction "VIN_42") (pintype "passive"))
      (node (ref "Dr.MOS1") (pin "8") (pinfunction "VIN_8") (pintype "passive"))
      (node (ref "Dr.MOS1") (pin "9") (pinfunction "VIN_9") (pintype "passive"))
      (node (ref "Dr.MOS2") (pin "10") (pinfunction "VIN_10") (pintype "passive"))
      (node (ref "Dr.MOS2") (pin "11") (pinfunction "VIN_11") (pintype "passive"))
      (node (ref "Dr.MOS2") (pin "12") (pinfunction "VIN_12") (pintype "passive"))
      (node (ref "Dr.MOS2") (pin "13") (pinfunction "VIN_13") (pintype "passive"))
      (node (ref "Dr.MOS2") (pin "14") (pinfunction "VIN_14") (pintype "passive"))
      (node (ref "Dr.MOS2") (pin "42") (pinfunction "VIN_42") (pintype "passive"))
      (node (ref "Dr.MOS2") (pin "8") (pinfunction "VIN_8") (pintype "passive"))
      (node (ref "Dr.MOS2") (pin "9") (pinfunction "VIN_9") (pintype "passive"))
      (node (ref "Dr.MOS3") (pin "10") (pinfunction "VIN_10") (pintype "passive"))
      (node (ref "Dr.MOS3") (pin "11") (pinfunction "VIN_11") (pintype "passive"))
      (node (ref "Dr.MOS3") (pin "12") (pinfunction "VIN_12") (pintype "passive"))
      (node (ref "Dr.MOS3") (pin "13") (pinfunction "VIN_13") (pintype "passive"))
      (node (ref "Dr.MOS3") (pin "14") (pinfunction "VIN_14") (pintype "passive"))
      (node (ref "Dr.MOS3") (pin "42") (pinfunction "VIN_42") (pintype "passive"))
      (node (ref "Dr.MOS3") (pin "8") (pinfunction "VIN_8") (pintype "passive"))
      (node (ref "Dr.MOS3") (pin "9") (pinfunction "VIN_9") (pintype "passive"))
      (node (ref "Dr.MOS4") (pin "10") (pinfunction "VIN_10") (pintype "passive"))
      (node (ref "Dr.MOS4") (pin "11") (pinfunction "VIN_11") (pintype "passive"))
      (node (ref "Dr.MOS4") (pin "12") (pinfunction "VIN_12") (pintype "passive"))
      (node (ref "Dr.MOS4") (pin "13") (pinfunction "VIN_13") (pintype "passive"))
      (node (ref "Dr.MOS4") (pin "14") (pinfunction "VIN_14") (pintype "passive"))
      (node (ref "Dr.MOS4") (pin "42") (pinfunction "VIN_42") (pintype "passive"))
      (node (ref "Dr.MOS4") (pin "8") (pinfunction "VIN_8") (pintype "passive"))
      (node (ref "Dr.MOS4") (pin "9") (pinfunction "VIN_9") (pintype "passive"))
      (node (ref "K1") (pin "2") (pinfunction "2_2") (pintype "passive"))
      (node (ref "K1") (pin "3") (pinfunction "3_3") (pintype "passive"))
      (node (ref "U1") (pin "3") (pinfunction "IN_3") (pintype "power_in"))
    )
    (net (code "33") (name "unconnected-(Dr.MOS1-GH-Pad6)") (class "Default")
      (node (ref "Dr.MOS1") (pin "6") (pinfunction "GH_6") (pintype "passive+no_connect"))
    )
    (net (code "34") (name "unconnected-(Dr.MOS1-GL-Pad36)") (class "Default")
      (node (ref "Dr.MOS1") (pin "36") (pinfunction "GL_36") (pintype "passive+no_connect"))
    )
    (net (code "35") (name "unconnected-(Dr.MOS1-THDN-Pad38)") (class "Default")
      (node (ref "Dr.MOS1") (pin "38") (pinfunction "THDN_38") (pintype "passive+no_connect"))
    )
    (net (code "36") (name "unconnected-(Dr.MOS2-GH-Pad6)") (class "Default")
      (node (ref "Dr.MOS2") (pin "6") (pinfunction "GH_6") (pintype "passive+no_connect"))
    )
    (net (code "37") (name "unconnected-(Dr.MOS2-GL-Pad36)") (class "Default")
      (node (ref "Dr.MOS2") (pin "36") (pinfunction "GL_36") (pintype "passive+no_connect"))
    )
    (net (code "38") (name "unconnected-(Dr.MOS2-THDN-Pad38)") (class "Default")
      (node (ref "Dr.MOS2") (pin "38") (pinfunction "THDN_38") (pintype "passive+no_connect"))
    )
    (net (code "39") (name "unconnected-(Dr.MOS3-GH-Pad6)") (class "Default")
      (node (ref "Dr.MOS3") (pin "6") (pinfunction "GH_6") (pintype "passive+no_connect"))
    )
    (net (code "40") (name "unconnected-(Dr.MOS3-GL-Pad36)") (class "Default")
      (node (ref "Dr.MOS3") (pin "36") (pinfunction "GL_36") (pintype "passive+no_connect"))
    )
    (net (code "41") (name "unconnected-(Dr.MOS3-THDN-Pad38)") (class "Default")
      (node (ref "Dr.MOS3") (pin "38") (pinfunction "THDN_38") (pintype "passive+no_connect"))
    )
    (net (code "42") (name "unconnected-(Dr.MOS4-GH-Pad6)") (class "Default")
      (node (ref "Dr.MOS4") (pin "6") (pinfunction "GH_6") (pintype "passive+no_connect"))
    )
    (net (code "43") (name "unconnected-(Dr.MOS4-GL-Pad36)") (class "Default")
      (node (ref "Dr.MOS4") (pin "36") (pinfunction "GL_36") (pintype "passive+no_connect"))
    )
    (net (code "44") (name "unconnected-(Dr.MOS4-THDN-Pad38)") (class "Default")
      (node (ref "Dr.MOS4") (pin "38") (pinfunction "THDN_38") (pintype "passive+no_connect"))
    )
  )
)
